# Another_flashlight.net
KiCad netlist of a schematic drawn in Altium Designer
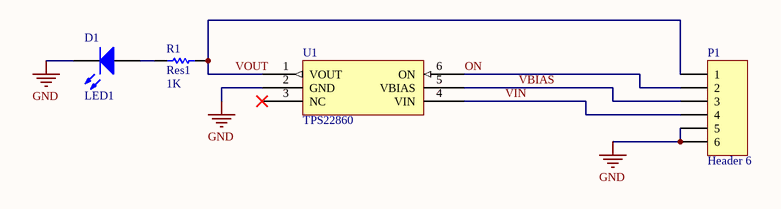
[diagram p0: Another_flashlight.SchDoc]

(export (version "E")
  (design (tool "Eeschema 10.0.6"))
  (components
    (comp (ref "D1")
      (value "LED1")
      (footprint "LED-1")
      (description "Typical RED GaAs LED")
      (fields (field (name "PUBLISHER") "Altium Limited"))
      (libsource (lib "Miscellaneous Devices") (part "LED1"))
    )
    (comp (ref "P1")
      (value "Header 6")
      (footprint "HDR1X6")
      (description "Header, 6-Pin")
      (fields (field (name "PUBLISHER") "Altium Limited"))
      (libsource (lib "Miscellaneous Connectors") (part "Header 6"))
    )
    (comp (ref "R1")
      (value "Res1")
      (footprint "AXIAL-0.3")
      (description "Resistor")
      (fields (field (name "ALTIUM_VALUE") "1K") (field (name "PUBLISHER") "Altium Limited"))
      (libsource (lib "Miscellaneous Devices") (part "Res1"))
    )
    (comp (ref "U1")
      (value "TPS22860")
      (footprint "TSOP95P280X145-6N")
      (libsource (lib "Another_flashlight") (part "TPS22860"))
    )
  )
  (nets
    (net (code "1") (name "/ON") (class "Default")
      (node (ref "P1") (pin "2") (pinfunction "2_2") (pintype "passive"))
      (node (ref "U1") (pin "6") (pinfunction "ON_6") (pintype "input"))
    )
    (net (code "2") (name "/VBIAS") (class "Default")
      (node (ref "P1") (pin "3") (pinfunction "3_3") (pintype "passive"))
      (node (ref "U1") (pin "5") (pinfunction "VBIAS_5") (pintype "power_in"))
    )
    (net (code "3") (name "/VIN") (class "Default")
      (node (ref "P1") (pin "4") (pinfunction "4_4") (pintype "passive"))
      (node (ref "U1") (pin "4") (pinfunction "VIN_4") (pintype "power_in"))
    )
    (net (code "4") (name "/VOUT") (class "Default")
      (node (ref "P1") (pin "1") (pinfunction "1_1") (pintype "passive"))
      (node (ref "R1") (pin "2") (pinfunction "2_2") (pintype "passive"))
      (node (ref "U1") (pin "1") (pinfunction "VOUT_1") (pintype "output"))
    )
    (net (code "5") (name "GND") (class "Default")
      (node (ref "D1") (pin "2") (pinfunction "K_2") (pintype "passive"))
      (node (ref "P1") (pin "5") (pinfunction "5_5") (pintype "passive"))
      (node (ref "P1") (pin "6") (pinfunction "6_6") (pintype "passive"))
      (node (ref "U1") (pin "2") (pinfunction "GND_2") (pintype "power_in"))
    )
    (net (code "6") (name "Net-(D1-A)") (class "Default")
      (node (ref "D1") (pin "1") (pinfunction "A_1") (pintype "passive"))
      (node (ref "R1") (pin "1") (pinfunction "1_1") (pintype "passive"))
    )
    (net (code "7") (name "unconnected-(U1-NC-Pad3)") (class "Default")
      (node (ref "U1") (pin "3") (pinfunction "NC_3") (pintype "passive+no_connect"))
    )
  )
)
